# Mainboard_Motordriver_Interface.net
KiCad netlist of a schematic drawn in Altium Designer
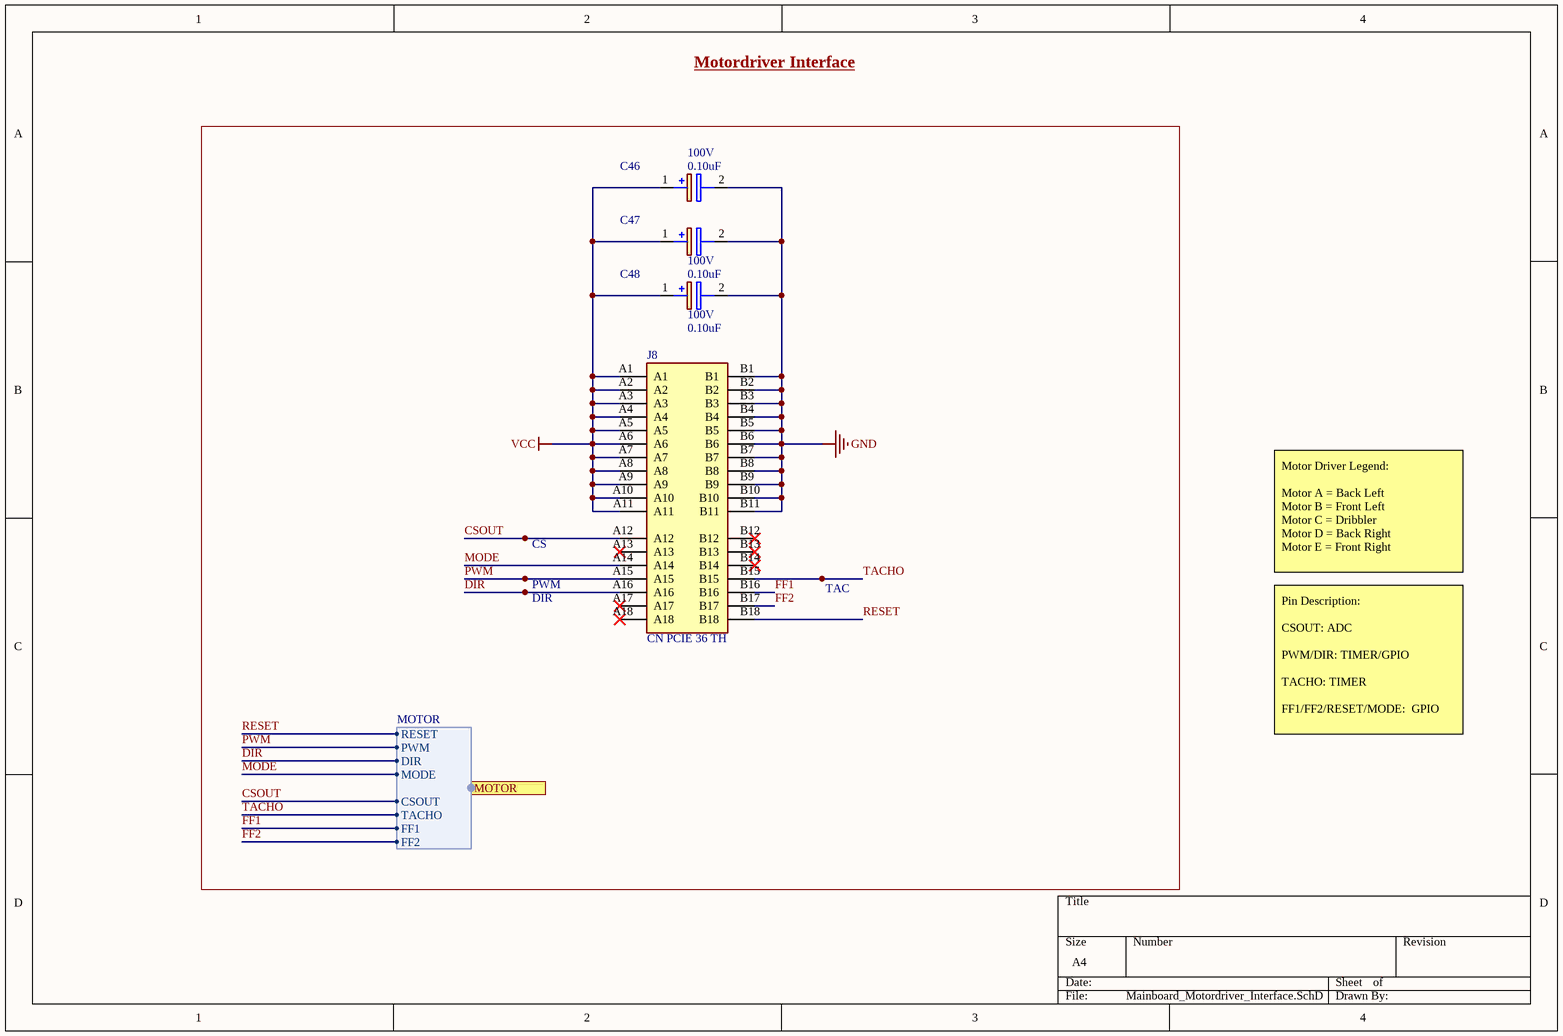
[diagram p0: Mainboard_Motordriver_Interface.SchDoc]

(export (version "E")
  (design (tool "Eeschema 10.0.6"))
  (components
    (comp (ref "C46")
      (value "0.10uF")
      (footprint "CAPPRD200W50D525H1250")
      (description "0.1µF 100V Aluminum Electrolytic Capacitors, Through-Hole, Radial, Can 2000 Hrs @ 85°C")
      (fields
        (field (name "MANUFACTURER_PART_NUMBER") "UKL2A0R1KDD")
        (field (name "MOUSER PART NUMBER") "647-UKL2A0R1KDD")
        (field (name "RATING") "100V")
      )
      (libsource (lib "AltiumLibraries") (part "CAP POL 0.1uF 100V"))
    )
    (comp (ref "C47")
      (value "0.10uF")
      (footprint "CAPPRD200W50D525H1250")
      (description "0.1µF 100V Aluminum Electrolytic Capacitors, Through-Hole, Radial, Can 2000 Hrs @ 85°C")
      (fields
        (field (name "MANUFACTURER_PART_NUMBER") "UKL2A0R1KDD")
        (field (name "MOUSER PART NUMBER") "647-UKL2A0R1KDD")
        (field (name "RATING") "100V")
      )
      (libsource (lib "AltiumLibraries") (part "CAP POL 0.1uF 100V"))
    )
    (comp (ref "C48")
      (value "0.10uF")
      (footprint "CAPPRD200W50D525H1250")
      (description "0.1µF 100V Aluminum Electrolytic Capacitors, Through-Hole, Radial, Can 2000 Hrs @ 85°C")
      (fields
        (field (name "MANUFACTURER_PART_NUMBER") "UKL2A0R1KDD")
        (field (name "MOUSER PART NUMBER") "647-UKL2A0R1KDD")
        (field (name "RATING") "100V")
      )
      (libsource (lib "AltiumLibraries") (part "CAP POL 0.1uF 100V"))
    )
    (comp (ref "CS")
      (value "Test Point (Via)")
      (footprint "TP")
      (libsource (lib "AltiumLibraries") (part "Test Point (Via)"))
    )
    (comp (ref "DIR")
      (value "Test Point (Via)")
      (footprint "TP")
      (libsource (lib "AltiumLibraries") (part "Test Point (Via)"))
    )
    (comp (ref "J8")
      (value "CN PCIE 36 TH")
      (footprint "CN PCIE 36 TH")
      (description "36 Position Female Connector PCI Expressâ„¢ Gold 0.039 _1.00mm_ Black 10018784-10210TLF")
      (fields (field (name "MP") "10018784-10210TLF") (field (name "MF") "Amphenol ICC"))
      (libsource (lib "AltiumLibraries") (part "CN PCIE 36 TH"))
    )
    (comp (ref "PWM")
      (value "Test Point (Via)")
      (footprint "TP")
      (libsource (lib "AltiumLibraries") (part "Test Point (Via)"))
    )
    (comp (ref "TAC")
      (value "Test Point (Via)")
      (footprint "TP")
      (libsource (lib "AltiumLibraries") (part "Test Point (Via)"))
    )
  )
  (nets
    (net (code "2") (name "/CSOUT") (class "Default")
      (node (ref "CS") (pin "1") (pinfunction "1_1") (pintype "passive"))
      (node (ref "J8") (pin "A12") (pinfunction "A12_A12") (pintype "passive"))
    )
    (net (code "3") (name "/DIR") (class "Default")
      (node (ref "DIR") (pin "1") (pinfunction "1_1") (pintype "passive"))
      (node (ref "J8") (pin "A16") (pinfunction "A16_A16") (pintype "passive"))
    )
    (net (code "4") (name "/FF1") (class "Default")
      (node (ref "J8") (pin "B16") (pinfunction "B16_B16") (pintype "passive"))
    )
    (net (code "5") (name "/FF2") (class "Default")
      (node (ref "J8") (pin "B17") (pinfunction "B17_B17") (pintype "passive"))
    )
    (net (code "6") (name "/MODE") (class "Default")
      (node (ref "J8") (pin "A14") (pinfunction "A14_A14") (pintype "passive"))
    )
    (net (code "7") (name "/PWM") (class "Default")
      (node (ref "J8") (pin "A15") (pinfunction "A15_A15") (pintype "passive"))
      (node (ref "PWM") (pin "1") (pinfunction "1_1") (pintype "passive"))
    )
    (net (code "8") (name "/RESET") (class "Default")
      (node (ref "J8") (pin "B18") (pinfunction "B18_B18") (pintype "passive"))
    )
    (net (code "9") (name "/TACHO") (class "Default")
      (node (ref "J8") (pin "B15") (pinfunction "B15_B15") (pintype "passive"))
      (node (ref "TAC") (pin "1") (pinfunction "1_1") (pintype "passive"))
    )
    (net (code "11") (name "GND") (class "Default")
      (node (ref "C46") (pin "2") (pinfunction "-_2") (pintype "passive"))
      (node (ref "C47") (pin "2") (pinfunction "-_2") (pintype "passive"))
      (node (ref "C48") (pin "2") (pinfunction "-_2") (pintype "passive"))
      (node (ref "J8") (pin "B1") (pinfunction "B1_B1") (pintype "passive"))
      (node (ref "J8") (pin "B10") (pinfunction "B10_B10") (pintype "passive"))
      (node (ref "J8") (pin "B11") (pinfunction "B11_B11") (pintype "passive"))
      (node (ref "J8") (pin "B2") (pinfunction "B2_B2") (pintype "passive"))
      (node (ref "J8") (pin "B3") (pinfunction "B3_B3") (pintype "passive"))
      (node (ref "J8") (pin "B4") (pinfunction "B4_B4") (pintype "passive"))
      (node (ref "J8") (pin "B5") (pinfunction "B5_B5") (pintype "passive"))
      (node (ref "J8") (pin "B6") (pinfunction "B6_B6") (pintype "passive"))
      (node (ref "J8") (pin "B7") (pinfunction "B7_B7") (pintype "passive"))
      (node (ref "J8") (pin "B8") (pinfunction "B8_B8") (pintype "passive"))
      (node (ref "J8") (pin "B9") (pinfunction "B9_B9") (pintype "passive"))
    )
    (net (code "12") (name "VCC") (class "Default")
      (node (ref "C46") (pin "1") (pinfunction "+_1") (pintype "passive"))
      (node (ref "C47") (pin "1") (pinfunction "+_1") (pintype "passive"))
      (node (ref "C48") (pin "1") (pinfunction "+_1") (pintype "passive"))
      (node (ref "J8") (pin "A1") (pinfunction "A1_A1") (pintype "passive"))
      (node (ref "J8") (pin "A10") (pinfunction "A10_A10") (pintype "passive"))
      (node (ref "J8") (pin "A11") (pinfunction "A11_A11") (pintype "passive"))
      (node (ref "J8") (pin "A2") (pinfunction "A2_A2") (pintype "passive"))
      (node (ref "J8") (pin "A3") (pinfunction "A3_A3") (pintype "passive"))
      (node (ref "J8") (pin "A4") (pinfunction "A4_A4") (pintype "passive"))
      (node (ref "J8") (pin "A5") (pinfunction "A5_A5") (pintype "passive"))
      (node (ref "J8") (pin "A6") (pinfunction "A6_A6") (pintype "passive"))
      (node (ref "J8") (pin "A7") (pinfunction "A7_A7") (pintype "passive"))
      (node (ref "J8") (pin "A8") (pinfunction "A8_A8") (pintype "passive"))
      (node (ref "J8") (pin "A9") (pinfunction "A9_A9") (pintype "passive"))
    )
    (net (code "13") (name "unconnected-(J8-PadA13)") (class "Default")
      (node (ref "J8") (pin "A13") (pinfunction "A13_A13") (pintype "passive+no_connect"))
    )
    (net (code "14") (name "unconnected-(J8-PadA17)") (class "Default")
      (node (ref "J8") (pin "A17") (pinfunction "A17_A17") (pintype "passive+no_connect"))
    )
    (net (code "15") (name "unconnected-(J8-PadA18)") (class "Default")
      (node (ref "J8") (pin "A18") (pinfunction "A18_A18") (pintype "passive+no_connect"))
    )
    (net (code "16") (name "unconnected-(J8-PadB12)") (class "Default")
      (node (ref "J8") (pin "B12") (pinfunction "B12_B12") (pintype "passive+no_connect"))
    )
    (net (code "17") (name "unconnected-(J8-PadB13)") (class "Default")
      (node (ref "J8") (pin "B13") (pinfunction "B13_B13") (pintype "passive+no_connect"))
    )
    (net (code "18") (name "unconnected-(J8-PadB14)") (class "Default")
      (node (ref "J8") (pin "B14") (pinfunction "B14_B14") (pintype "passive+no_connect"))
    )
  )
)
